# mc.net
KiCad netlist of a schematic drawn in EAGLE
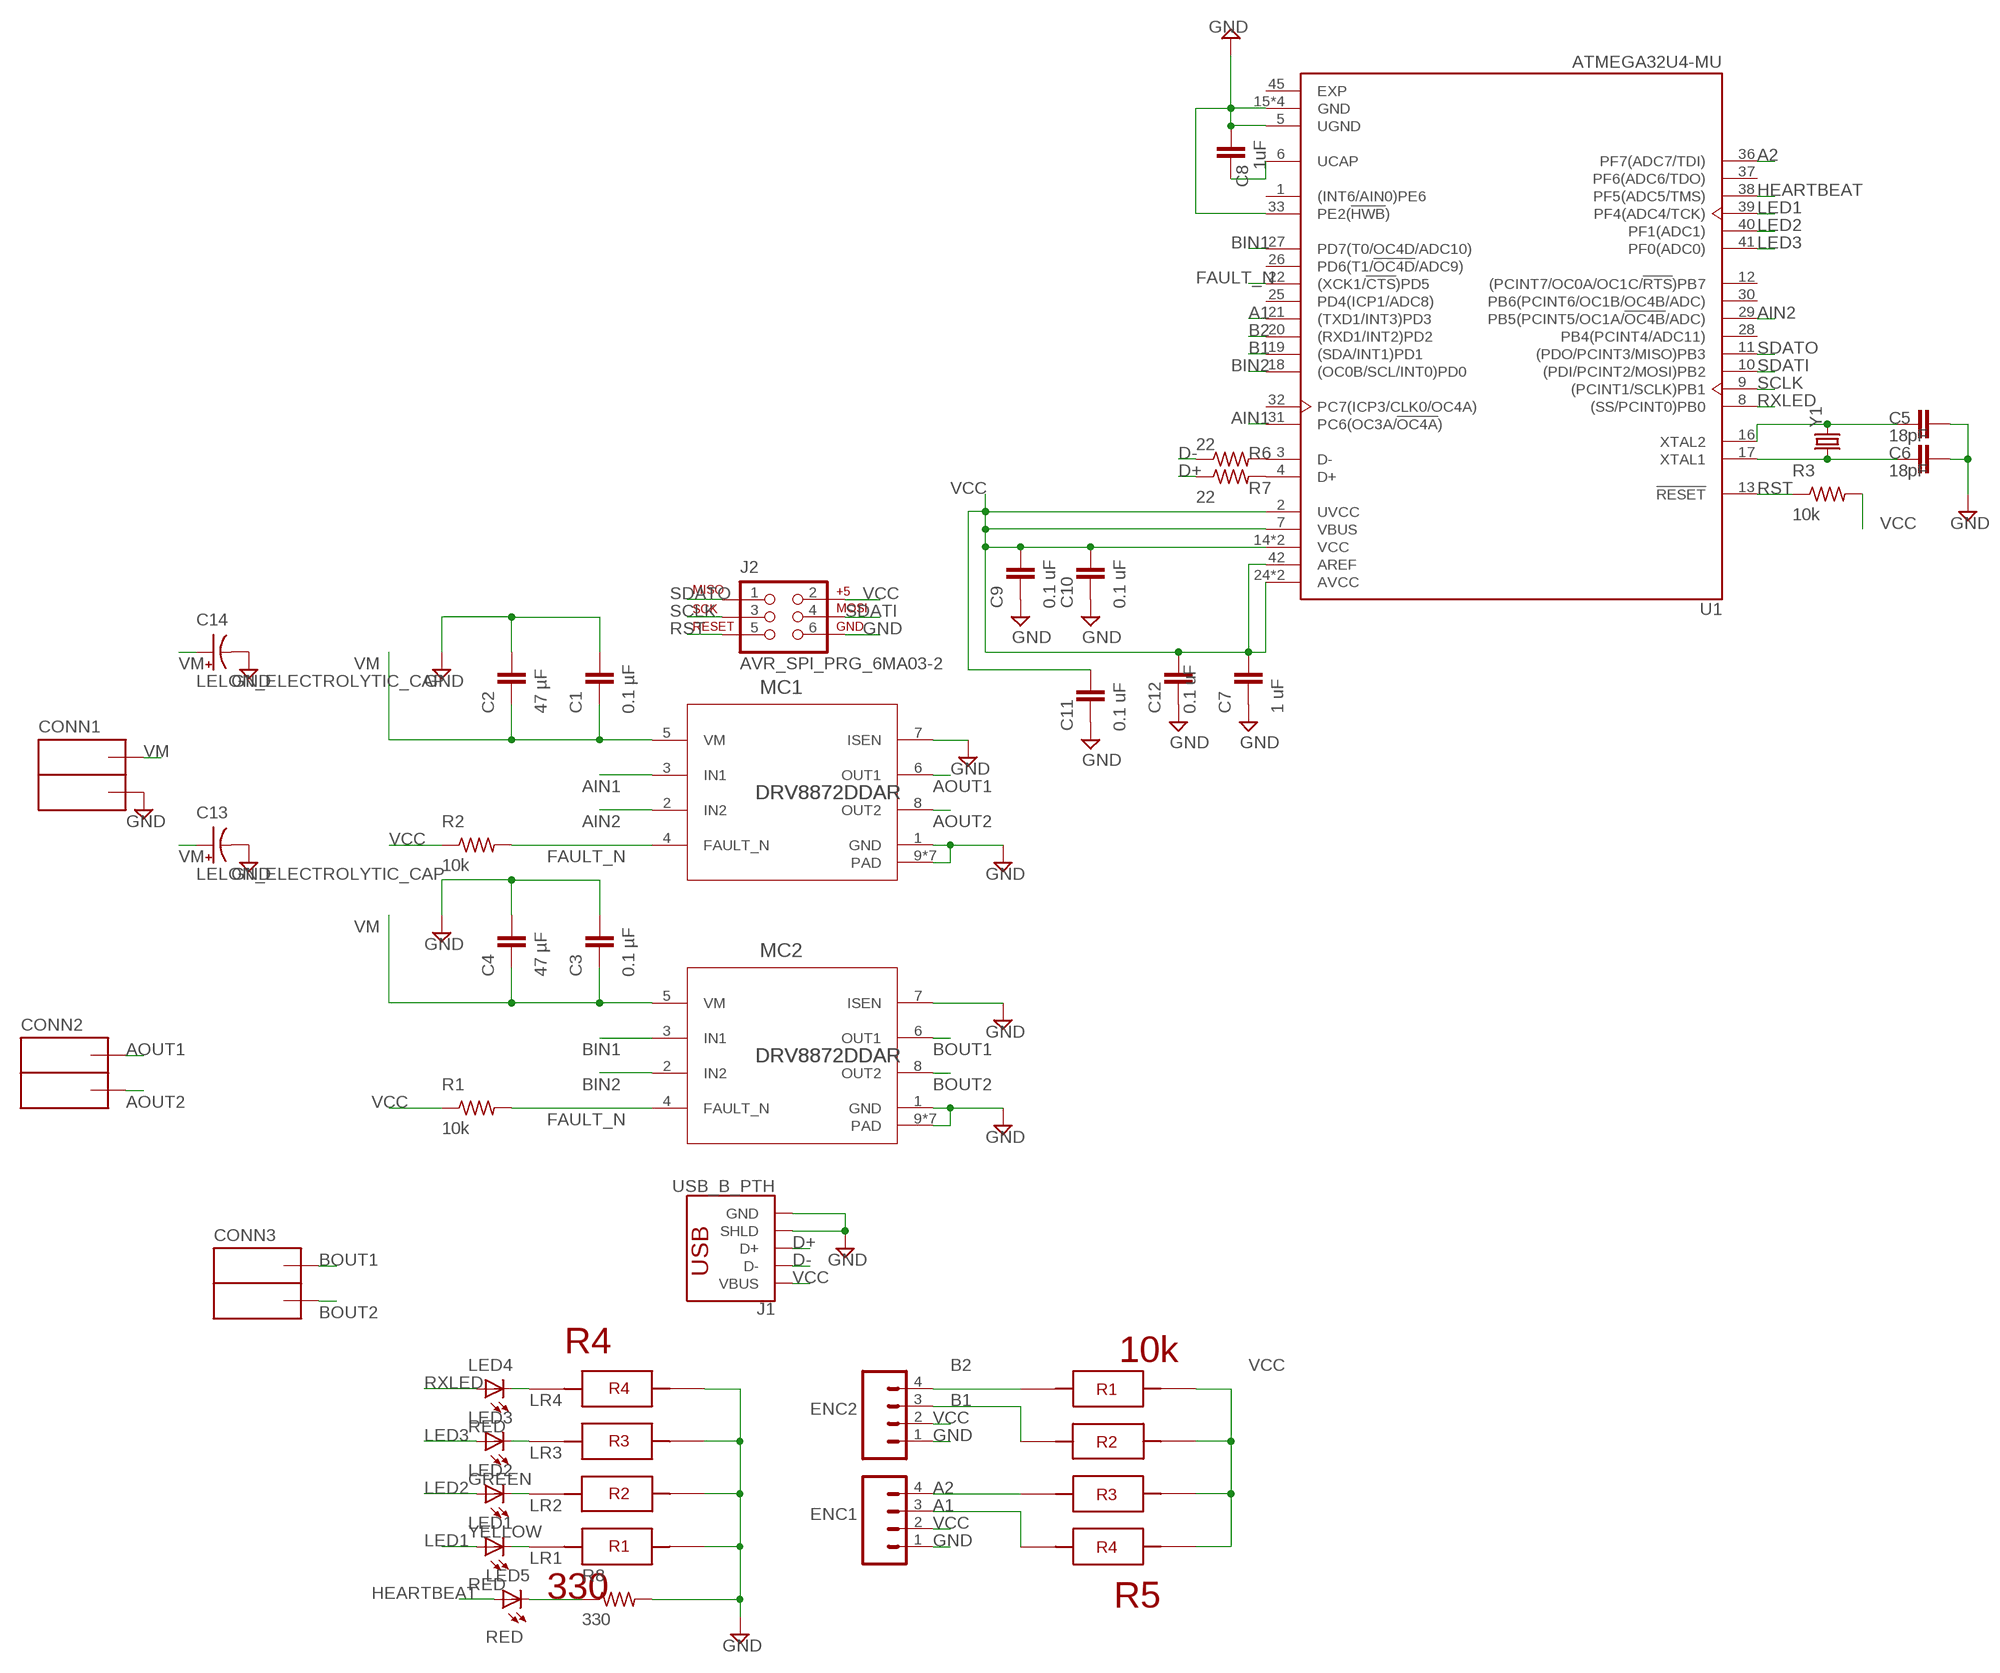
[diagram p0: schematic, sheet 1]

(export (version "E")
  (design (tool "Eeschema 10.0.6"))
  (components
    (comp (ref "C1")
      (value "0.1 µF")
      (footprint "eagle-import:0603-CAP")
      (libsource (lib "eagle-import") (part "CAP0603-CAP"))
    )
    (comp (ref "C2")
      (value "47 µF")
      (footprint "eagle-import:1206")
      (libsource (lib "eagle-import") (part "CAP1206"))
    )
    (comp (ref "C3")
      (value "0.1 µF")
      (footprint "eagle-import:0603-CAP")
      (libsource (lib "eagle-import") (part "CAP0603-CAP"))
    )
    (comp (ref "C4")
      (value "47 µF")
      (footprint "eagle-import:1206")
      (libsource (lib "eagle-import") (part "CAP1206"))
    )
    (comp (ref "C5")
      (value "18pF")
      (footprint "eagle-import:0603-CAP")
      (libsource (lib "eagle-import") (part "CAP0603-CAP"))
    )
    (comp (ref "C6")
      (value "18pF")
      (footprint "eagle-import:0603-CAP")
      (libsource (lib "eagle-import") (part "CAP0603-CAP"))
    )
    (comp (ref "C7")
      (value "1 uF")
      (footprint "eagle-import:0603-CAP")
      (libsource (lib "eagle-import") (part "CAP0603-CAP"))
    )
    (comp (ref "C8")
      (value "1uF")
      (footprint "eagle-import:0603-CAP")
      (libsource (lib "eagle-import") (part "CAP0603-CAP"))
    )
    (comp (ref "C9")
      (value "0.1 uF")
      (footprint "eagle-import:0402-CAP")
      (libsource (lib "eagle-import") (part "CAP0402-CAP"))
    )
    (comp (ref "C10")
      (value "0.1 uF")
      (footprint "eagle-import:0402-CAP")
      (libsource (lib "eagle-import") (part "CAP0402-CAP"))
    )
    (comp (ref "C11")
      (value "0.1 uF")
      (footprint "eagle-import:0402-CAP")
      (libsource (lib "eagle-import") (part "CAP0402-CAP"))
    )
    (comp (ref "C12")
      (value "0.1 uF")
      (footprint "eagle-import:0402-CAP")
      (libsource (lib "eagle-import") (part "CAP0402-CAP"))
    )
    (comp (ref "C13")
      (value "LELON_ELECTROLYTIC_CAP")
      (footprint "eagle-import:LELON_CAP")
      (libsource (lib "eagle-import") (part "LELON_ELECTROLYTIC_CAP"))
    )
    (comp (ref "C14")
      (value "LELON_ELECTROLYTIC_CAP")
      (footprint "eagle-import:LELON_CAP")
      (libsource (lib "eagle-import") (part "LELON_ELECTROLYTIC_CAP"))
    )
    (comp (ref "CONN1")
      (value "ANDERSONVERTICAL")
      (footprint "eagle-import:ANDERSON_VERTICAL")
      (libsource (lib "eagle-import") (part "ANDERSONVERTICAL"))
    )
    (comp (ref "CONN2")
      (value "ANDERSONVERTICAL")
      (footprint "eagle-import:ANDERSON_VERTICAL")
      (libsource (lib "eagle-import") (part "ANDERSONVERTICAL"))
    )
    (comp (ref "CONN3")
      (value "ANDERSONVERTICAL")
      (footprint "eagle-import:ANDERSON_VERTICAL")
      (libsource (lib "eagle-import") (part "ANDERSONVERTICAL"))
    )
    (comp (ref "ENC1")
      (value "M041X04-MTA")
      (footprint "eagle-import:1X04-MTA")
      (libsource (lib "eagle-import") (part "M041X04-MTA"))
    )
    (comp (ref "ENC2")
      (value "M041X04-MTA")
      (footprint "eagle-import:1X04-MTA")
      (libsource (lib "eagle-import") (part "M041X04-MTA"))
    )
    (comp (ref "J1")
      (value "USB_B_PTH")
      (footprint "eagle-import:USB-B-PTH")
      (libsource (lib "eagle-import") (part "USB_B_PTH"))
    )
    (comp (ref "J2")
      (value "AVR_SPI_PRG_6MA03-2")
      (footprint "eagle-import:MA03-2")
      (libsource (lib "eagle-import") (part "AVR_SPI_PRG_6MA03-2"))
    )
    (comp (ref "LED1")
      (value "RED")
      (footprint "eagle-import:LED-0805")
      (libsource (lib "eagle-import") (part "LED0805"))
    )
    (comp (ref "LED2")
      (value "YELLOW")
      (footprint "eagle-import:LED-0805")
      (libsource (lib "eagle-import") (part "LED0805"))
    )
    (comp (ref "LED3")
      (value "GREEN")
      (footprint "eagle-import:LED-0805")
      (libsource (lib "eagle-import") (part "LED0805"))
    )
    (comp (ref "LED4")
      (value "RED")
      (footprint "eagle-import:LED-0805")
      (libsource (lib "eagle-import") (part "LED0805"))
    )
    (comp (ref "LED5")
      (value "RED")
      (footprint "eagle-import:LED-0805")
      (libsource (lib "eagle-import") (part "LED0805"))
    )
    (comp (ref "MC1")
      (value "DRV8872DDAR")
      (footprint "eagle-import:DDA0008H_N_TEX")
      (libsource (lib "eagle-import") (part "DRV8872DDAR"))
    )
    (comp (ref "MC2")
      (value "DRV8872DDAR")
      (footprint "eagle-import:DDA0008H_N_TEX")
      (libsource (lib "eagle-import") (part "DRV8872DDAR"))
    )
    (comp (ref "R1")
      (value "10k")
      (footprint "eagle-import:R0603")
      (fields (field (name "MANUFACTURER") "Rohm Semiconductor"))
      (libsource (lib "eagle-import") (part "R-US_R0603"))
    )
    (comp (ref "R2")
      (value "10k")
      (footprint "eagle-import:R0603")
      (fields (field (name "MANUFACTURER") "Rohm Semiconductor"))
      (libsource (lib "eagle-import") (part "R-US_R0603"))
    )
    (comp (ref "R3")
      (value "10k")
      (footprint "eagle-import:R0603")
      (fields (field (name "MANUFACTURER") "Rohm Semiconductor"))
      (libsource (lib "eagle-import") (part "R-US_R0603"))
    )
    (comp (ref "R4")
      (value "330")
      (footprint "eagle-import:4X-0603")
      (libsource (lib "eagle-import") (part "4X-0603"))
    )
    (comp (ref "R5")
      (value "10k")
      (footprint "eagle-import:4X-0603")
      (libsource (lib "eagle-import") (part "4X-0603"))
    )
    (comp (ref "R6")
      (value "22")
      (footprint "eagle-import:R0603")
      (fields (field (name "MANUFACTURER") "Rohm Semiconductor"))
      (libsource (lib "eagle-import") (part "R-US_R0603"))
    )
    (comp (ref "R7")
      (value "22")
      (footprint "eagle-import:R0603")
      (fields (field (name "MANUFACTURER") "Rohm Semiconductor"))
      (libsource (lib "eagle-import") (part "R-US_R0603"))
    )
    (comp (ref "R8")
      (value "330")
      (footprint "eagle-import:R0603")
      (fields (field (name "MANUFACTURER") "Rohm Semiconductor"))
      (libsource (lib "eagle-import") (part "R-US_R0603"))
    )
    (comp (ref "U1")
      (value "ATMEGA32U4-MU")
      (footprint "eagle-import:QFN50P700X700X100-45N")
      (fields (field (name "MF") "Microchip"))
      (libsource (lib "eagle-import") (part "ATMEGA32U4-MU"))
    )
    (comp (ref "Y1")
      (value "CRYSTAL")
      (footprint "eagle-import:CRYSTAL-SMD-5.0X3.2-2PIN")
      (libsource (lib "eagle-import") (part "CRYSTAL"))
    )
  )
  (nets
    (net (code "1") (name "/A1") (class "Default")
      (node (ref "ENC1") (pin "3") (pinfunction "3_3") (pintype "passive"))
      (node (ref "R5") (pin "4") (pinfunction "4_4") (pintype "bidirectional"))
      (node (ref "U1") (pin "21") (pinfunction "(TXD1/INT3)PD3_21") (pintype "bidirectional"))
    )
    (net (code "2") (name "/A2") (class "Default")
      (node (ref "ENC1") (pin "4") (pinfunction "4_4") (pintype "passive"))
      (node (ref "R5") (pin "3") (pinfunction "3_3") (pintype "bidirectional"))
      (node (ref "U1") (pin "36") (pinfunction "PF7(ADC7/TDI)_36") (pintype "bidirectional"))
    )
    (net (code "3") (name "/AIN1") (class "Default")
      (node (ref "MC1") (pin "3") (pinfunction "IN1_3") (pintype "input"))
      (node (ref "U1") (pin "31") (pinfunction "PC6(OC3A/~{OC4A})_31") (pintype "bidirectional"))
    )
    (net (code "4") (name "/AIN2") (class "Default")
      (node (ref "MC1") (pin "2") (pinfunction "IN2_2") (pintype "input"))
      (node (ref "U1") (pin "29") (pinfunction "PB5(PCINT5/OC1A/~{OC4B}/ADC)_29") (pintype "bidirectional"))
    )
    (net (code "5") (name "/AOUT1") (class "Default")
      (node (ref "CONN2") (pin "PIN2") (pinfunction "OUTA_PIN2") (pintype "bidirectional"))
      (node (ref "MC1") (pin "6") (pinfunction "OUT1_6") (pintype "output"))
    )
    (net (code "6") (name "/AOUT2") (class "Default")
      (node (ref "CONN2") (pin "PIN1") (pinfunction "OUTB_PIN1") (pintype "bidirectional"))
      (node (ref "MC1") (pin "8") (pinfunction "OUT2_8") (pintype "output"))
    )
    (net (code "7") (name "/B1") (class "Default")
      (node (ref "ENC2") (pin "3") (pinfunction "3_3") (pintype "passive"))
      (node (ref "R5") (pin "2") (pinfunction "2_2") (pintype "bidirectional"))
      (node (ref "U1") (pin "19") (pinfunction "(SDA/INT1)PD1_19") (pintype "bidirectional"))
    )
    (net (code "8") (name "/B2") (class "Default")
      (node (ref "ENC2") (pin "4") (pinfunction "4_4") (pintype "passive"))
      (node (ref "R5") (pin "1") (pinfunction "1_1") (pintype "bidirectional"))
      (node (ref "U1") (pin "20") (pinfunction "(RXD1/INT2)PD2_20") (pintype "bidirectional"))
    )
    (net (code "9") (name "/BIN1") (class "Default")
      (node (ref "MC2") (pin "3") (pinfunction "IN1_3") (pintype "input"))
      (node (ref "U1") (pin "27") (pinfunction "PD7(T0/OC4D/ADC10)_27") (pintype "bidirectional"))
    )
    (net (code "10") (name "/BIN2") (class "Default")
      (node (ref "MC2") (pin "2") (pinfunction "IN2_2") (pintype "input"))
      (node (ref "U1") (pin "18") (pinfunction "(OC0B/SCL/INT0)PD0_18") (pintype "bidirectional"))
    )
    (net (code "11") (name "/BOUT1") (class "Default")
      (node (ref "CONN3") (pin "PIN2") (pinfunction "OUTA_PIN2") (pintype "bidirectional"))
      (node (ref "MC2") (pin "6") (pinfunction "OUT1_6") (pintype "output"))
    )
    (net (code "12") (name "/BOUT2") (class "Default")
      (node (ref "CONN3") (pin "PIN1") (pinfunction "OUTB_PIN1") (pintype "bidirectional"))
      (node (ref "MC2") (pin "8") (pinfunction "OUT2_8") (pintype "output"))
    )
    (net (code "13") (name "/D+") (class "Default")
      (node (ref "J1") (pin "D+") (pinfunction "D+_D+") (pintype "bidirectional"))
      (node (ref "R7") (pin "1") (pinfunction "1_1") (pintype "passive"))
    )
    (net (code "14") (name "/D-") (class "Default")
      (node (ref "J1") (pin "D-") (pinfunction "D-_D-") (pintype "bidirectional"))
      (node (ref "R6") (pin "1") (pinfunction "1_1") (pintype "passive"))
    )
    (net (code "15") (name "/FAULT_N") (class "Default")
      (node (ref "MC1") (pin "4") (pinfunction "FAULT_N_4") (pintype "open_collector"))
      (node (ref "MC2") (pin "4") (pinfunction "FAULT_N_4") (pintype "open_collector"))
      (node (ref "R1") (pin "2") (pinfunction "2_2") (pintype "passive"))
      (node (ref "R2") (pin "2") (pinfunction "2_2") (pintype "passive"))
      (node (ref "U1") (pin "22") (pinfunction "(XCK1/~{CTS})PD5_22") (pintype "bidirectional"))
    )
    (net (code "16") (name "/HEARTBEAT") (class "Default")
      (node (ref "LED5") (pin "A") (pinfunction "A_A") (pintype "passive"))
      (node (ref "U1") (pin "38") (pinfunction "PF5(ADC5/TMS)_38") (pintype "bidirectional"))
    )
    (net (code "17") (name "/LED1") (class "Default")
      (node (ref "LED1") (pin "A") (pinfunction "A_A") (pintype "passive"))
      (node (ref "U1") (pin "39") (pinfunction "PF4(ADC4/TCK)_39") (pintype "bidirectional"))
    )
    (net (code "18") (name "/LED2") (class "Default")
      (node (ref "LED2") (pin "A") (pinfunction "A_A") (pintype "passive"))
      (node (ref "U1") (pin "40") (pinfunction "PF1(ADC1)_40") (pintype "bidirectional"))
    )
    (net (code "19") (name "/LED3") (class "Default")
      (node (ref "LED3") (pin "A") (pinfunction "A_A") (pintype "passive"))
      (node (ref "U1") (pin "41") (pinfunction "PF0(ADC0)_41") (pintype "bidirectional"))
    )
    (net (code "20") (name "/LR1") (class "Default")
      (node (ref "LED1") (pin "C") (pinfunction "C_C") (pintype "passive"))
      (node (ref "R4") (pin "8") (pinfunction "8_8") (pintype "bidirectional"))
    )
    (net (code "21") (name "/LR2") (class "Default")
      (node (ref "LED2") (pin "C") (pinfunction "C_C") (pintype "passive"))
      (node (ref "R4") (pin "7") (pinfunction "7_7") (pintype "bidirectional"))
    )
    (net (code "22") (name "/LR3") (class "Default")
      (node (ref "LED3") (pin "C") (pinfunction "C_C") (pintype "passive"))
      (node (ref "R4") (pin "6") (pinfunction "6_6") (pintype "bidirectional"))
    )
    (net (code "23") (name "/LR4") (class "Default")
      (node (ref "LED4") (pin "C") (pinfunction "C_C") (pintype "passive"))
      (node (ref "R4") (pin "5") (pinfunction "5_5") (pintype "bidirectional"))
    )
    (net (code "24") (name "/RST") (class "Default")
      (node (ref "J2") (pin "5") (pinfunction "5_5") (pintype "passive"))
      (node (ref "R3") (pin "1") (pinfunction "1_1") (pintype "passive"))
      (node (ref "U1") (pin "13") (pinfunction "~{RESET}_13") (pintype "input"))
    )
    (net (code "25") (name "/RXLED") (class "Default")
      (node (ref "LED4") (pin "A") (pinfunction "A_A") (pintype "passive"))
      (node (ref "U1") (pin "8") (pinfunction "(SS/PCINT0)PB0_8") (pintype "bidirectional"))
    )
    (net (code "26") (name "/SCLK") (class "Default")
      (node (ref "J2") (pin "3") (pinfunction "3_3") (pintype "passive"))
      (node (ref "U1") (pin "9") (pinfunction "(PCINT1/SCLK)PB1_9") (pintype "bidirectional"))
    )
    (net (code "27") (name "/SDATI") (class "Default")
      (node (ref "J2") (pin "4") (pinfunction "4_4") (pintype "passive"))
      (node (ref "U1") (pin "10") (pinfunction "(PDI/PCINT2/MOSI)PB2_10") (pintype "bidirectional"))
    )
    (net (code "28") (name "/SDATO") (class "Default")
      (node (ref "J2") (pin "1") (pinfunction "1_1") (pintype "passive"))
      (node (ref "U1") (pin "11") (pinfunction "(PDO/PCINT3/MISO)PB3_11") (pintype "bidirectional"))
    )
    (net (code "29") (name "/VCC") (class "Default")
      (node (ref "C10") (pin "2") (pinfunction "2_2") (pintype "passive"))
      (node (ref "C11") (pin "2") (pinfunction "2_2") (pintype "passive"))
      (node (ref "C12") (pin "2") (pinfunction "2_2") (pintype "passive"))
      (node (ref "C7") (pin "2") (pinfunction "2_2") (pintype "passive"))
      (node (ref "C9") (pin "2") (pinfunction "2_2") (pintype "passive"))
      (node (ref "ENC1") (pin "2") (pinfunction "2_2") (pintype "passive"))
      (node (ref "ENC2") (pin "2") (pinfunction "2_2") (pintype "passive"))
      (node (ref "J1") (pin "VBUS") (pinfunction "VBUS_VBUS") (pintype "power_in"))
      (node (ref "J2") (pin "2") (pinfunction "2_2") (pintype "passive"))
      (node (ref "R1") (pin "1") (pinfunction "1_1") (pintype "passive"))
      (node (ref "R2") (pin "1") (pinfunction "1_1") (pintype "passive"))
      (node (ref "R3") (pin "2") (pinfunction "2_2") (pintype "passive"))
      (node (ref "R5") (pin "5") (pinfunction "5_5") (pintype "bidirectional"))
      (node (ref "R5") (pin "6") (pinfunction "6_6") (pintype "bidirectional"))
      (node (ref "R5") (pin "7") (pinfunction "7_7") (pintype "bidirectional"))
      (node (ref "R5") (pin "8") (pinfunction "8_8") (pintype "bidirectional"))
      (node (ref "U1") (pin "14") (pinfunction "VCC_14") (pintype "power_in"))
      (node (ref "U1") (pin "2") (pinfunction "UVCC_2") (pintype "power_in"))
      (node (ref "U1") (pin "24") (pinfunction "AVCC_24") (pintype "power_in"))
      (node (ref "U1") (pin "34") (pinfunction "VCC_34") (pintype "power_in"))
      (node (ref "U1") (pin "42") (pinfunction "AREF_42") (pintype "power_in"))
      (node (ref "U1") (pin "44") (pinfunction "AVCC_44") (pintype "power_in"))
      (node (ref "U1") (pin "7") (pinfunction "VBUS_7") (pintype "power_in"))
    )
    (net (code "30") (name "/VM") (class "Default")
      (node (ref "C1") (pin "1") (pinfunction "1_1") (pintype "passive"))
      (node (ref "C13") (pin "P$1") (pinfunction "+_P$1") (pintype "passive"))
      (node (ref "C14") (pin "P$1") (pinfunction "+_P$1") (pintype "passive"))
      (node (ref "C2") (pin "1") (pinfunction "1_1") (pintype "passive"))
      (node (ref "C3") (pin "1") (pinfunction "1_1") (pintype "passive"))
      (node (ref "C4") (pin "1") (pinfunction "1_1") (pintype "passive"))
      (node (ref "CONN1") (pin "PIN2") (pinfunction "OUTA_PIN2") (pintype "bidirectional"))
      (node (ref "MC1") (pin "5") (pinfunction "VM_5") (pintype "power_in"))
      (node (ref "MC2") (pin "5") (pinfunction "VM_5") (pintype "power_in"))
    )
    (net (code "31") (name "GND") (class "Default")
      (node (ref "C1") (pin "2") (pinfunction "2_2") (pintype "passive"))
      (node (ref "C10") (pin "1") (pinfunction "1_1") (pintype "passive"))
      (node (ref "C11") (pin "1") (pinfunction "1_1") (pintype "passive"))
      (node (ref "C12") (pin "1") (pinfunction "1_1") (pintype "passive"))
      (node (ref "C13") (pin "P$2") (pinfunction "-_P$2") (pintype "passive"))
      (node (ref "C14") (pin "P$2") (pinfunction "-_P$2") (pintype "passive"))
      (node (ref "C2") (pin "2") (pinfunction "2_2") (pintype "passive"))
      (node (ref "C3") (pin "2") (pinfunction "2_2") (pintype "passive"))
      (node (ref "C4") (pin "2") (pinfunction "2_2") (pintype "passive"))
      (node (ref "C5") (pin "2") (pinfunction "2_2") (pintype "passive"))
      (node (ref "C6") (pin "2") (pinfunction "2_2") (pintype "passive"))
      (node (ref "C7") (pin "1") (pinfunction "1_1") (pintype "passive"))
      (node (ref "C8") (pin "2") (pinfunction "2_2") (pintype "passive"))
      (node (ref "C9") (pin "1") (pinfunction "1_1") (pintype "passive"))
      (node (ref "CONN1") (pin "PIN1") (pinfunction "OUTB_PIN1") (pintype "bidirectional"))
      (node (ref "ENC1") (pin "1") (pinfunction "1_1") (pintype "passive"))
      (node (ref "ENC2") (pin "1") (pinfunction "1_1") (pintype "passive"))
      (node (ref "J1") (pin "GND") (pinfunction "GND_GND") (pintype "power_in"))
      (node (ref "J1") (pin "SHLD1") (pinfunction "SHLD_SHLD1") (pintype "bidirectional"))
      (node (ref "J1") (pin "SHLD2") (pinfunction "SHLD_SHLD2") (pintype "bidirectional"))
      (node (ref "J2") (pin "6") (pinfunction "6_6") (pintype "passive"))
      (node (ref "MC1") (pin "1") (pinfunction "GND_1") (pintype "power_in"))
      (node (ref "MC1") (pin "7") (pinfunction "ISEN_7") (pintype "input"))
      (node (ref "MC1") (pin "9") (pinfunction "PAD_9") (pintype "power_in"))
      (node (ref "MC1") (pin "P$1") (pinfunction "PAD_P$1") (pintype "power_in"))
      (node (ref "MC1") (pin "P$2") (pinfunction "PAD_P$2") (pintype "power_in"))
      (node (ref "MC1") (pin "P$3") (pinfunction "PAD_P$3") (pintype "power_in"))
      (node (ref "MC1") (pin "P$4") (pinfunction "PAD_P$4") (pintype "power_in"))
      (node (ref "MC1") (pin "P$5") (pinfunction "PAD_P$5") (pintype "power_in"))
      (node (ref "MC1") (pin "P$6") (pinfunction "PAD_P$6") (pintype "power_in"))
      (node (ref "MC2") (pin "1") (pinfunction "GND_1") (pintype "power_in"))
      (node (ref "MC2") (pin "7") (pinfunction "ISEN_7") (pintype "input"))
      (node (ref "MC2") (pin "9") (pinfunction "PAD_9") (pintype "power_in"))
      (node (ref "MC2") (pin "P$1") (pinfunction "PAD_P$1") (pintype "power_in"))
      (node (ref "MC2") (pin "P$2") (pinfunction "PAD_P$2") (pintype "power_in"))
      (node (ref "MC2") (pin "P$3") (pinfunction "PAD_P$3") (pintype "power_in"))
      (node (ref "MC2") (pin "P$4") (pinfunction "PAD_P$4") (pintype "power_in"))
      (node (ref "MC2") (pin "P$5") (pinfunction "PAD_P$5") (pintype "power_in"))
      (node (ref "MC2") (pin "P$6") (pinfunction "PAD_P$6") (pintype "power_in"))
      (node (ref "R4") (pin "1") (pinfunction "1_1") (pintype "bidirectional"))
      (node (ref "R4") (pin "2") (pinfunction "2_2") (pintype "bidirectional"))
      (node (ref "R4") (pin "3") (pinfunction "3_3") (pintype "bidirectional"))
      (node (ref "R4") (pin "4") (pinfunction "4_4") (pintype "bidirectional"))
      (node (ref "R8") (pin "2") (pinfunction "2_2") (pintype "passive"))
      (node (ref "U1") (pin "15") (pinfunction "GND_15") (pintype "power_in"))
      (node (ref "U1") (pin "23") (pinfunction "GND_23") (pintype "power_in"))
      (node (ref "U1") (pin "33") (pinfunction "PE2(~{HWB})_33") (pintype "bidirectional"))
      (node (ref "U1") (pin "35") (pinfunction "GND_35") (pintype "power_in"))
      (node (ref "U1") (pin "43") (pinfunction "GND_43") (pintype "power_in"))
      (node (ref "U1") (pin "5") (pinfunction "UGND_5") (pintype "power_in"))
    )
    (net (code "32") (name "Net-(LED5-PadC)") (class "Default")
      (node (ref "LED5") (pin "C") (pinfunction "C_C") (pintype "passive"))
      (node (ref "R8") (pin "1") (pinfunction "1_1") (pintype "passive"))
    )
    (net (code "33") (name "Net-(U1-D+)") (class "Default")
      (node (ref "R7") (pin "2") (pinfunction "2_2") (pintype "passive"))
      (node (ref "U1") (pin "4") (pinfunction "D+_4") (pintype "bidirectional"))
    )
    (net (code "34") (name "Net-(U1-D-)") (class "Default")
      (node (ref "R6") (pin "2") (pinfunction "2_2") (pintype "passive"))
      (node (ref "U1") (pin "3") (pinfunction "D-_3") (pintype "bidirectional"))
    )
    (net (code "35") (name "Net-(U1-UCAP)") (class "Default")
      (node (ref "C8") (pin "1") (pinfunction "1_1") (pintype "passive"))
      (node (ref "U1") (pin "6") (pinfunction "UCAP_6") (pintype "passive"))
    )
    (net (code "36") (name "Net-(U1-XTAL1)") (class "Default")
      (node (ref "C6") (pin "1") (pinfunction "1_1") (pintype "passive"))
      (node (ref "U1") (pin "17") (pinfunction "XTAL1_17") (pintype "input"))
      (node (ref "Y1") (pin "P$2") (pinfunction "2_P$2") (pintype "passive"))
    )
    (net (code "37") (name "Net-(U1-XTAL2)") (class "Default")
      (node (ref "C5") (pin "1") (pinfunction "1_1") (pintype "passive"))
      (node (ref "U1") (pin "16") (pinfunction "XTAL2_16") (pintype "output"))
      (node (ref "Y1") (pin "P$1") (pinfunction "1_P$1") (pintype "passive"))
    )
    (net (code "38") (name "unconnected-(U1-(INT6{slash}AIN0)PE6-Pad1)") (class "Default")
      (node (ref "U1") (pin "1") (pinfunction "(INT6/AIN0)PE6_1") (pintype "bidirectional"))
    )
    (net (code "39") (name "unconnected-(U1-(PCINT7{slash}OC0A{slash}OC1C{slash}~{RTS})PB7-Pad12)") (class "Default")
      (node (ref "U1") (pin "12") (pinfunction "(PCINT7/OC0A/OC1C/~{RTS})PB7_12") (pintype "bidirectional"))
    )
    (net (code "40") (name "unconnected-(U1-EXP-Pad45)") (class "Default")
      (node (ref "U1") (pin "45") (pinfunction "EXP_45") (pintype "passive"))
    )
    (net (code "41") (name "unconnected-(U1-PB4(PCINT4{slash}ADC11)-Pad28)") (class "Default")
      (node (ref "U1") (pin "28") (pinfunction "PB4(PCINT4/ADC11)_28") (pintype "bidirectional"))
    )
    (net (code "42") (name "unconnected-(U1-PB6(PCINT6{slash}OC1B{slash}OC4B{slash}ADC)-Pad30)") (class "Default")
      (node (ref "U1") (pin "30") (pinfunction "PB6(PCINT6/OC1B/OC4B/ADC)_30") (pintype "bidirectional"))
    )
    (net (code "43") (name "unconnected-(U1-PC7(ICP3{slash}CLK0{slash}OC4A)-Pad32)") (class "Default")
      (node (ref "U1") (pin "32") (pinfunction "PC7(ICP3/CLK0/OC4A)_32") (pintype "bidirectional"))
    )
    (net (code "44") (name "unconnected-(U1-PD4(ICP1{slash}ADC8)-Pad25)") (class "Default")
      (node (ref "U1") (pin "25") (pinfunction "PD4(ICP1/ADC8)_25") (pintype "bidirectional"))
    )
    (net (code "45") (name "unconnected-(U1-PD6(T1{slash}~{OC4D}{slash}ADC9)-Pad26)") (class "Default")
      (node (ref "U1") (pin "26") (pinfunction "PD6(T1/~{OC4D}/ADC9)_26") (pintype "bidirectional"))
    )
    (net (code "46") (name "unconnected-(U1-PF6(ADC6{slash}TDO)-Pad37)") (class "Default")
      (node (ref "U1") (pin "37") (pinfunction "PF6(ADC6/TDO)_37") (pintype "bidirectional"))
    )
  )
)
